# 34.net
KiCad netlist of a schematic drawn in Altium Designer
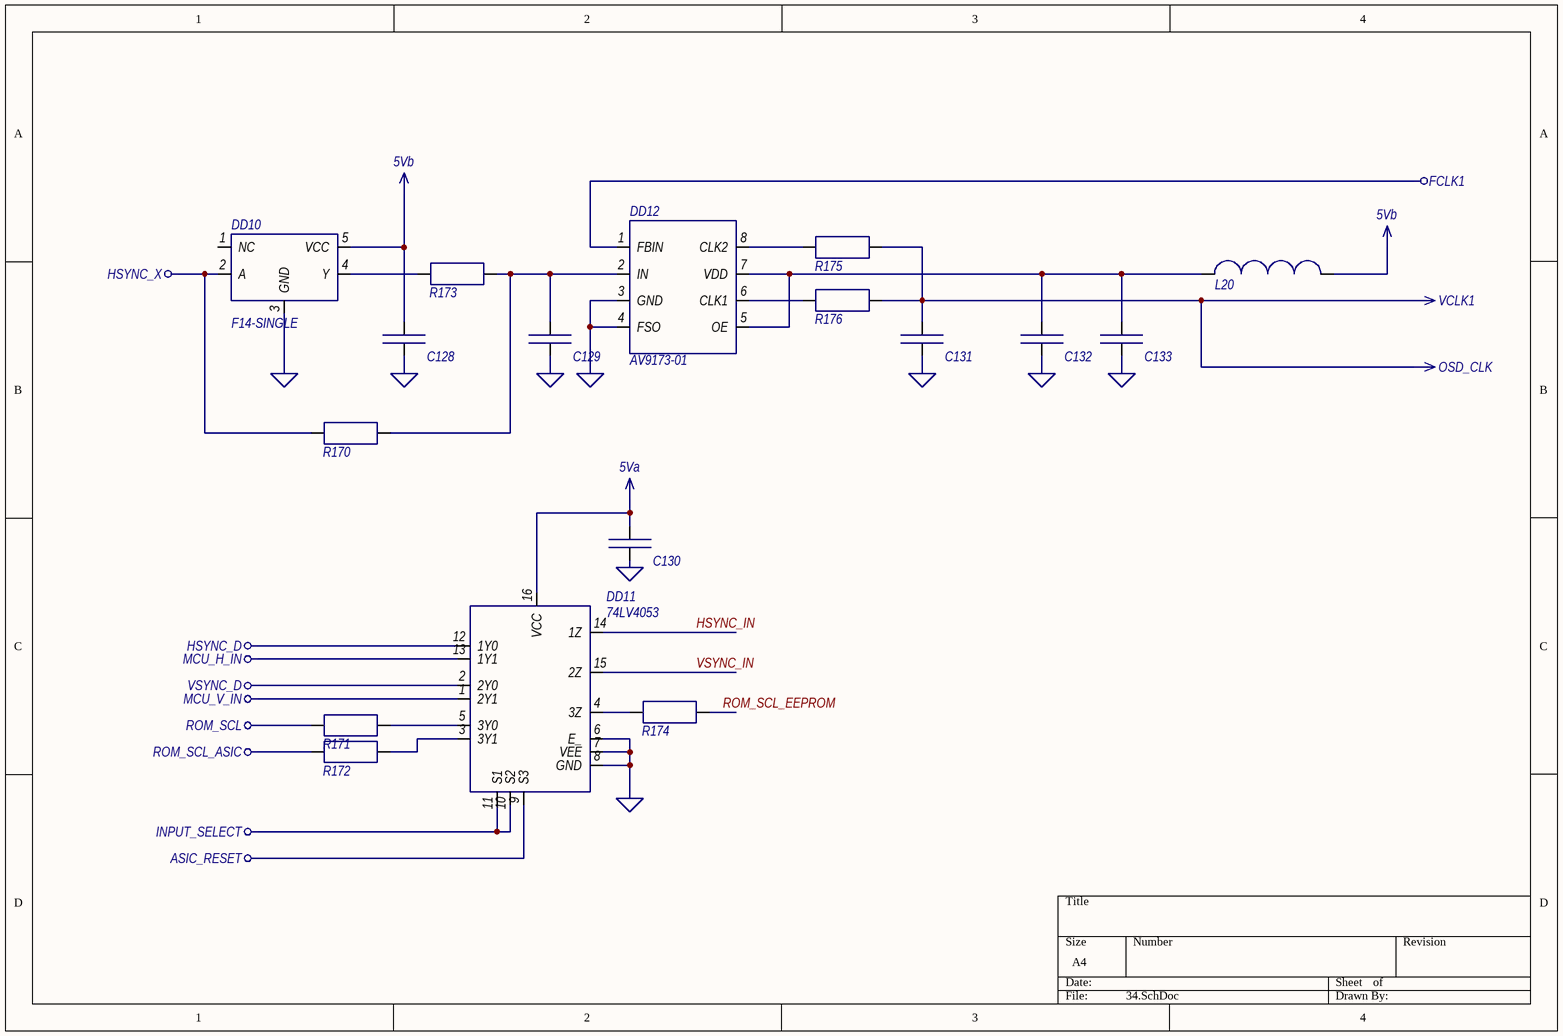
[diagram p0: 34.SchDoc]

(export (version "E")
  (design (tool "Eeschema 10.0.6"))
  (components
    (comp (ref "C128")
      (value "Capacitor")
      (footprint "cap_electro_13")
      (libsource (lib "31_lib") (part "Capacitor"))
    )
    (comp (ref "C129")
      (value "Capacitor")
      (footprint "cap_electro_13")
      (libsource (lib "31_lib") (part "Capacitor"))
    )
    (comp (ref "C130")
      (value "Capacitor")
      (footprint "cap_electro_13")
      (libsource (lib "31_lib") (part "Capacitor"))
    )
    (comp (ref "C131")
      (value "Capacitor")
      (footprint "cap_electro_13")
      (libsource (lib "31_lib") (part "Capacitor"))
    )
    (comp (ref "C132")
      (value "Capacitor")
      (footprint "cap_electro_13")
      (libsource (lib "31_lib") (part "Capacitor"))
    )
    (comp (ref "C133")
      (value "Capacitor")
      (footprint "cap_electro_13")
      (libsource (lib "31_lib") (part "Capacitor"))
    )
    (comp (ref "DD10")
      (value "F14-SINGLE")
      (footprint "74AHC1G14(SOT25)")
      (libsource (lib "31_lib") (part "74AHC1G14-TA"))
    )
    (comp (ref "DD11")
      (value "74LV4053")
      (footprint "31_lib:74LV4053(SOT38-4)")
      (libsource (lib "31_lib") (part "74LV4053"))
    )
    (comp (ref "DD12")
      (value "AV9173-01")
      (footprint "31_lib:AV9173-01(DIP8)")
      (libsource (lib "31_lib") (part "AV9173-01"))
    )
    (comp (ref "L20")
      (value "Inductor")
      (footprint "31_lib:inductor")
      (libsource (lib "31_lib") (part "Inductor"))
    )
    (comp (ref "R170")
      (value "Resistor")
      (footprint "lab_7_footprints:R_1206")
      (libsource (lib "31_lib") (part "Resistor"))
    )
    (comp (ref "R171")
      (value "Resistor")
      (footprint "lab_7_footprints:R_1206")
      (libsource (lib "31_lib") (part "Resistor"))
    )
    (comp (ref "R172")
      (value "Resistor")
      (footprint "lab_7_footprints:R_1206")
      (libsource (lib "31_lib") (part "Resistor"))
    )
    (comp (ref "R173")
      (value "Resistor")
      (footprint "lab_7_footprints:R_1206")
      (libsource (lib "31_lib") (part "Resistor"))
    )
    (comp (ref "R174")
      (value "Resistor")
      (footprint "lab_7_footprints:R_1206")
      (libsource (lib "31_lib") (part "Resistor"))
    )
    (comp (ref "R175")
      (value "Resistor")
      (footprint "lab_7_footprints:R_1206")
      (libsource (lib "31_lib") (part "Resistor"))
    )
    (comp (ref "R176")
      (value "Resistor")
      (footprint "lab_7_footprints:R_1206")
      (libsource (lib "31_lib") (part "Resistor"))
    )
  )
  (nets
    (net (code "1") (name "/HSYNC_IN") (class "Default")
      (node (ref "DD11") (pin "14") (pinfunction "1Z_14") (pintype "passive"))
    )
    (net (code "2") (name "/ROM_SCL_EEPROM") (class "Default")
      (node (ref "R174") (pin "2") (pinfunction "2_2") (pintype "passive"))
    )
    (net (code "3") (name "/VSYNC_IN") (class "Default")
      (node (ref "DD11") (pin "15") (pinfunction "2Z_15") (pintype "passive"))
    )
    (net (code "4") (name "5Va") (class "Default")
      (node (ref "C130") (pin "2") (pinfunction "2_2") (pintype "passive"))
      (node (ref "DD11") (pin "16") (pinfunction "VCC_16") (pintype "passive"))
    )
    (net (code "5") (name "5Vb") (class "Default")
      (node (ref "C128") (pin "1") (pinfunction "1_1") (pintype "passive"))
      (node (ref "DD10") (pin "5") (pinfunction "VCC_5") (pintype "passive"))
      (node (ref "L20") (pin "2") (pinfunction "2_2") (pintype "passive"))
    )
    (net (code "6") (name "ASIC_RESET") (class "Default")
      (node (ref "DD11") (pin "9") (pinfunction "S3_9") (pintype "passive"))
    )
    (net (code "7") (name "FCLK1") (class "Default")
      (node (ref "DD12") (pin "1") (pinfunction "FBIN_1") (pintype "passive"))
    )
    (net (code "8") (name "GND") (class "Default")
      (node (ref "C128") (pin "2") (pinfunction "2_2") (pintype "passive"))
      (node (ref "C129") (pin "2") (pinfunction "2_2") (pintype "passive"))
      (node (ref "C130") (pin "1") (pinfunction "1_1") (pintype "passive"))
      (node (ref "C131") (pin "2") (pinfunction "2_2") (pintype "passive"))
      (node (ref "C132") (pin "2") (pinfunction "2_2") (pintype "passive"))
      (node (ref "C133") (pin "2") (pinfunction "2_2") (pintype "passive"))
      (node (ref "DD10") (pin "3") (pinfunction "GND_3") (pintype "passive"))
      (node (ref "DD11") (pin "6") (pinfunction "E__6") (pintype "passive"))
      (node (ref "DD11") (pin "7") (pinfunction "VEE_7") (pintype "passive"))
      (node (ref "DD11") (pin "8") (pinfunction "GND_8") (pintype "passive"))
      (node (ref "DD12") (pin "3") (pinfunction "GND_3") (pintype "passive"))
      (node (ref "DD12") (pin "4") (pinfunction "FSO_4") (pintype "passive"))
    )
    (net (code "9") (name "HSYNC_D") (class "Default")
      (node (ref "DD11") (pin "12") (pinfunction "1Y0_12") (pintype "passive"))
    )
    (net (code "10") (name "HSYNC_X") (class "Default")
      (node (ref "DD10") (pin "2") (pinfunction "A_2") (pintype "passive"))
      (node (ref "R170") (pin "1") (pinfunction "1_1") (pintype "passive"))
    )
    (net (code "11") (name "INPUT_SELECT") (class "Default")
      (node (ref "DD11") (pin "10") (pinfunction "S2_10") (pintype "passive"))
      (node (ref "DD11") (pin "11") (pinfunction "S1_11") (pintype "passive"))
    )
    (net (code "12") (name "MCU_H_IN") (class "Default")
      (node (ref "DD11") (pin "13") (pinfunction "1Y1_13") (pintype "passive"))
    )
    (net (code "13") (name "MCU_V_IN") (class "Default")
      (node (ref "DD11") (pin "1") (pinfunction "2Y1_1") (pintype "passive"))
    )
    (net (code "14") (name "Net-(DD10-Y)") (class "Default")
      (node (ref "DD10") (pin "4") (pinfunction "Y_4") (pintype "passive"))
      (node (ref "R173") (pin "1") (pinfunction "1_1") (pintype "passive"))
    )
    (net (code "15") (name "Net-(DD11-3Y0)") (class "Default")
      (node (ref "DD11") (pin "5") (pinfunction "3Y0_5") (pintype "passive"))
      (node (ref "R171") (pin "2") (pinfunction "2_2") (pintype "passive"))
    )
    (net (code "16") (name "Net-(DD11-3Y1)") (class "Default")
      (node (ref "DD11") (pin "3") (pinfunction "3Y1_3") (pintype "passive"))
      (node (ref "R172") (pin "2") (pinfunction "2_2") (pintype "passive"))
    )
    (net (code "17") (name "Net-(DD11-3Z)") (class "Default")
      (node (ref "DD11") (pin "4") (pinfunction "3Z_4") (pintype "passive"))
      (node (ref "R174") (pin "1") (pinfunction "1_1") (pintype "passive"))
    )
    (net (code "18") (name "Net-(DD12-CLK1)") (class "Default")
      (node (ref "DD12") (pin "6") (pinfunction "CLK1_6") (pintype "passive"))
      (node (ref "R176") (pin "1") (pinfunction "1_1") (pintype "passive"))
    )
    (net (code "19") (name "Net-(DD12-CLK2)") (class "Default")
      (node (ref "DD12") (pin "8") (pinfunction "CLK2_8") (pintype "passive"))
      (node (ref "R175") (pin "1") (pinfunction "1_1") (pintype "passive"))
    )
    (net (code "20") (name "Net-(DD12-IN)") (class "Default")
      (node (ref "C129") (pin "1") (pinfunction "1_1") (pintype "passive"))
      (node (ref "DD12") (pin "2") (pinfunction "IN_2") (pintype "passive"))
      (node (ref "R170") (pin "2") (pinfunction "2_2") (pintype "passive"))
      (node (ref "R173") (pin "2") (pinfunction "2_2") (pintype "passive"))
    )
    (net (code "21") (name "Net-(DD12-OE)") (class "Default")
      (node (ref "C132") (pin "1") (pinfunction "1_1") (pintype "passive"))
      (node (ref "C133") (pin "1") (pinfunction "1_1") (pintype "passive"))
      (node (ref "DD12") (pin "5") (pinfunction "OE_5") (pintype "passive"))
      (node (ref "DD12") (pin "7") (pinfunction "VDD_7") (pintype "passive"))
      (node (ref "L20") (pin "1") (pinfunction "1_1") (pintype "passive"))
    )
    (net (code "22") (name "OSD_CLK") (class "Default")
      (node (ref "C131") (pin "1") (pinfunction "1_1") (pintype "passive"))
      (node (ref "R175") (pin "2") (pinfunction "2_2") (pintype "passive"))
      (node (ref "R176") (pin "2") (pinfunction "2_2") (pintype "passive"))
    )
    (net (code "23") (name "ROM_SCL") (class "Default")
      (node (ref "R171") (pin "1") (pinfunction "1_1") (pintype "passive"))
    )
    (net (code "24") (name "ROM_SCL_ASIC") (class "Default")
      (node (ref "R172") (pin "1") (pinfunction "1_1") (pintype "passive"))
    )
    (net (code "25") (name "VSYNC_D") (class "Default")
      (node (ref "DD11") (pin "2") (pinfunction "2Y0_2") (pintype "passive"))
    )
    (net (code "26") (name "unconnected-(DD10-NC-Pad1)") (class "Default")
      (node (ref "DD10") (pin "1") (pinfunction "NC_1") (pintype "passive"))
    )
  )
)
